# ADC_channel_4.net
KiCad netlist of a schematic drawn in EAGLE
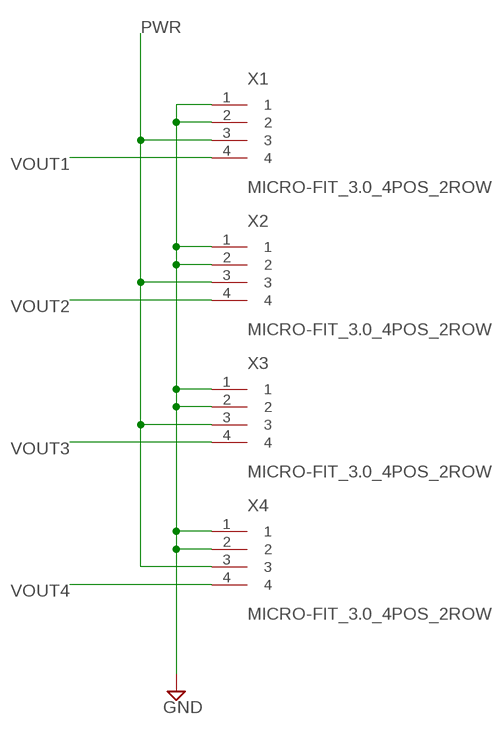
[diagram p0: schematic, sheet 1]

(export (version "E")
  (design (tool "Eeschema 10.0.6"))
  (components
    (comp (ref "X1")
      (value "MICRO-FIT_3.0_4POS_2ROW")
      (footprint "eagle-import:0430450412")
      (fields (field (name "MANUFACTURER") "Molex"))
      (libsource (lib "eagle-import") (part "MICRO-FIT_3.0_4POS_2ROW"))
    )
    (comp (ref "X2")
      (value "MICRO-FIT_3.0_4POS_2ROW")
      (footprint "eagle-import:0430450412")
      (fields (field (name "MANUFACTURER") "Molex"))
      (libsource (lib "eagle-import") (part "MICRO-FIT_3.0_4POS_2ROW"))
    )
    (comp (ref "X3")
      (value "MICRO-FIT_3.0_4POS_2ROW")
      (footprint "eagle-import:0430450412")
      (fields (field (name "MANUFACTURER") "Molex"))
      (libsource (lib "eagle-import") (part "MICRO-FIT_3.0_4POS_2ROW"))
    )
    (comp (ref "X4")
      (value "MICRO-FIT_3.0_4POS_2ROW")
      (footprint "eagle-import:0430450412")
      (fields (field (name "MANUFACTURER") "Molex"))
      (libsource (lib "eagle-import") (part "MICRO-FIT_3.0_4POS_2ROW"))
    )
  )
  (nets
    (net (code "1") (name "/PWR") (class "Default")
      (node (ref "X1") (pin "3") (pinfunction "3_3") (pintype "bidirectional"))
      (node (ref "X2") (pin "3") (pinfunction "3_3") (pintype "bidirectional"))
      (node (ref "X3") (pin "3") (pinfunction "3_3") (pintype "bidirectional"))
      (node (ref "X4") (pin "3") (pinfunction "3_3") (pintype "bidirectional"))
    )
    (net (code "2") (name "/VOUT1") (class "Default")
      (node (ref "X1") (pin "4") (pinfunction "4_4") (pintype "bidirectional"))
    )
    (net (code "3") (name "/VOUT2") (class "Default")
      (node (ref "X2") (pin "4") (pinfunction "4_4") (pintype "bidirectional"))
    )
    (net (code "4") (name "/VOUT3") (class "Default")
      (node (ref "X3") (pin "4") (pinfunction "4_4") (pintype "bidirectional"))
    )
    (net (code "5") (name "/VOUT4") (class "Default")
      (node (ref "X4") (pin "4") (pinfunction "4_4") (pintype "bidirectional"))
    )
    (net (code "6") (name "GND") (class "Default")
      (node (ref "X1") (pin "1") (pinfunction "1_1") (pintype "bidirectional"))
      (node (ref "X1") (pin "2") (pinfunction "2_2") (pintype "bidirectional"))
      (node (ref "X2") (pin "1") (pinfunction "1_1") (pintype "bidirectional"))
      (node (ref "X2") (pin "2") (pinfunction "2_2") (pintype "bidirectional"))
      (node (ref "X3") (pin "1") (pinfunction "1_1") (pintype "bidirectional"))
      (node (ref "X3") (pin "2") (pinfunction "2_2") (pintype "bidirectional"))
      (node (ref "X4") (pin "1") (pinfunction "1_1") (pintype "bidirectional"))
      (node (ref "X4") (pin "2") (pinfunction "2_2") (pintype "bidirectional"))
    )
  )
)
